# Attenumults_Rev_6.net
KiCad netlist of a schematic drawn in EAGLE
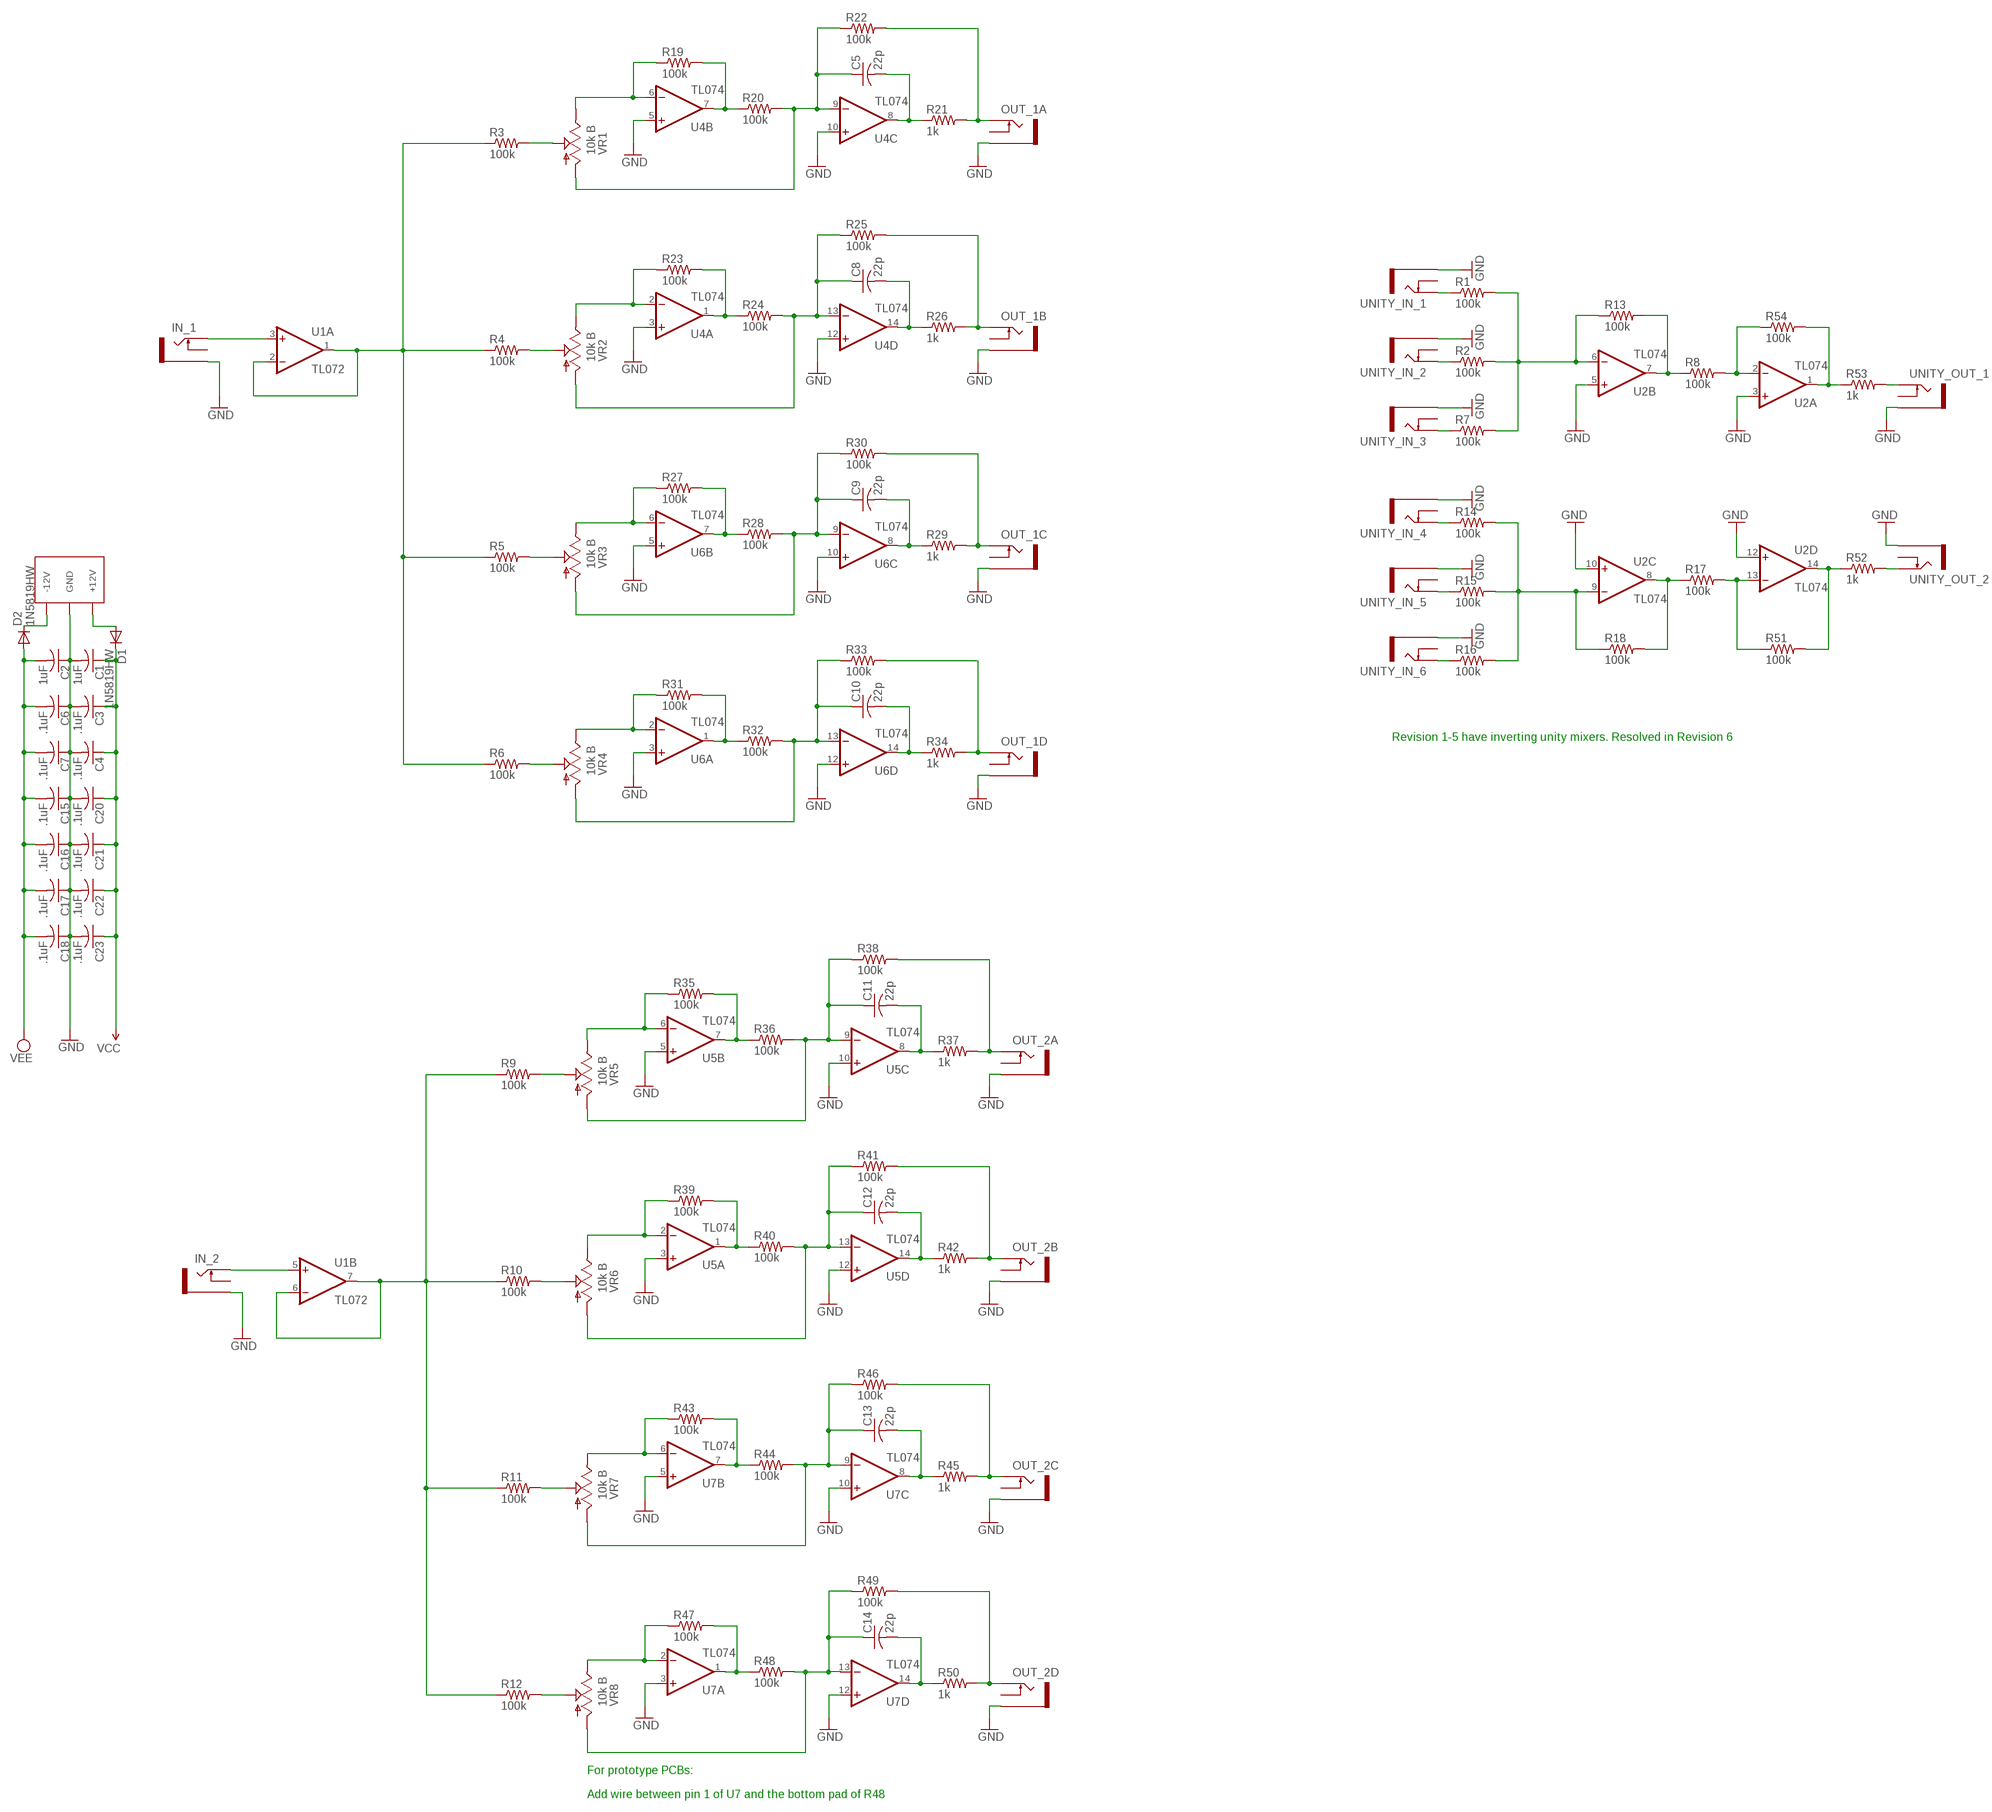
[diagram p0: schematic, sheet 1]

(export (version "E")
  (design (tool "Eeschema 10.0.6"))
  (components
    (comp (ref "C1")
      (value "1uF")
      (footprint "eagle-import:C0805")
      (libsource (lib "eagle-import") (part "C-USC0805"))
    )
    (comp (ref "C2")
      (value "1uF")
      (footprint "eagle-import:C0805")
      (libsource (lib "eagle-import") (part "C-USC0805"))
    )
    (comp (ref "C3")
      (value ".1uF")
      (footprint "eagle-import:C0805")
      (libsource (lib "eagle-import") (part "C-USC0805"))
    )
    (comp (ref "C4")
      (value ".1uF")
      (footprint "eagle-import:C0805")
      (libsource (lib "eagle-import") (part "C-USC0805"))
    )
    (comp (ref "C5")
      (value "22p")
      (footprint "eagle-import:C0805")
      (libsource (lib "eagle-import") (part "C-USC0805"))
    )
    (comp (ref "C6")
      (value ".1uF")
      (footprint "eagle-import:C0805")
      (libsource (lib "eagle-import") (part "C-USC0805"))
    )
    (comp (ref "C7")
      (value ".1uF")
      (footprint "eagle-import:C0805")
      (libsource (lib "eagle-import") (part "C-USC0805"))
    )
    (comp (ref "C8")
      (value "22p")
      (footprint "eagle-import:C0805")
      (libsource (lib "eagle-import") (part "C-USC0805"))
    )
    (comp (ref "C9")
      (value "22p")
      (footprint "eagle-import:C0805")
      (libsource (lib "eagle-import") (part "C-USC0805"))
    )
    (comp (ref "C10")
      (value "22p")
      (footprint "eagle-import:C0805")
      (libsource (lib "eagle-import") (part "C-USC0805"))
    )
    (comp (ref "C11")
      (value "22p")
      (footprint "eagle-import:C0805")
      (libsource (lib "eagle-import") (part "C-USC0805"))
    )
    (comp (ref "C12")
      (value "22p")
      (footprint "eagle-import:C0805")
      (libsource (lib "eagle-import") (part "C-USC0805"))
    )
    (comp (ref "C13")
      (value "22p")
      (footprint "eagle-import:C0805")
      (libsource (lib "eagle-import") (part "C-USC0805"))
    )
    (comp (ref "C14")
      (value "22p")
      (footprint "eagle-import:C0805")
      (libsource (lib "eagle-import") (part "C-USC0805"))
    )
    (comp (ref "C15")
      (value ".1uF")
      (footprint "eagle-import:C0805")
      (libsource (lib "eagle-import") (part "C-USC0805"))
    )
    (comp (ref "C16")
      (value ".1uF")
      (footprint "eagle-import:C0805")
      (libsource (lib "eagle-import") (part "C-USC0805"))
    )
    (comp (ref "C17")
      (value ".1uF")
      (footprint "eagle-import:C0805")
      (libsource (lib "eagle-import") (part "C-USC0805"))
    )
    (comp (ref "C18")
      (value ".1uF")
      (footprint "eagle-import:C0805")
      (libsource (lib "eagle-import") (part "C-USC0805"))
    )
    (comp (ref "C20")
      (value ".1uF")
      (footprint "eagle-import:C0805")
      (libsource (lib "eagle-import") (part "C-USC0805"))
    )
    (comp (ref "C21")
      (value ".1uF")
      (footprint "eagle-import:C0805")
      (libsource (lib "eagle-import") (part "C-USC0805"))
    )
    (comp (ref "C22")
      (value ".1uF")
      (footprint "eagle-import:C0805")
      (libsource (lib "eagle-import") (part "C-USC0805"))
    )
    (comp (ref "C23")
      (value ".1uF")
      (footprint "eagle-import:C0805")
      (libsource (lib "eagle-import") (part "C-USC0805"))
    )
    (comp (ref "D1")
      (value "1N5819HW")
      (footprint "eagle-import:SOD123")
      (libsource (lib "eagle-import") (part "DIODE-SOD123"))
    )
    (comp (ref "D2")
      (value "1N5819HW")
      (footprint "eagle-import:SOD123")
      (libsource (lib "eagle-import") (part "DIODE-SOD123"))
    )
    (comp (ref "IN_1")
      (value "THONKICONNNEW")
      (footprint "eagle-import:WQP-PJ301M-12_JACK")
      (libsource (lib "eagle-import") (part "THONKICONNNEW"))
    )
    (comp (ref "IN_2")
      (value "THONKICONNNEW")
      (footprint "eagle-import:WQP-PJ301M-12_JACK")
      (libsource (lib "eagle-import") (part "THONKICONNNEW"))
    )
    (comp (ref "OUT_1A")
      (value "THONKICONNNEW")
      (footprint "eagle-import:WQP-PJ301M-12_JACK")
      (libsource (lib "eagle-import") (part "THONKICONNNEW"))
    )
    (comp (ref "OUT_1B")
      (value "THONKICONNNEW")
      (footprint "eagle-import:WQP-PJ301M-12_JACK")
      (libsource (lib "eagle-import") (part "THONKICONNNEW"))
    )
    (comp (ref "OUT_1C")
      (value "THONKICONNNEW")
      (footprint "eagle-import:WQP-PJ301M-12_JACK")
      (libsource (lib "eagle-import") (part "THONKICONNNEW"))
    )
    (comp (ref "OUT_1D")
      (value "THONKICONNNEW")
      (footprint "eagle-import:WQP-PJ301M-12_JACK")
      (libsource (lib "eagle-import") (part "THONKICONNNEW"))
    )
    (comp (ref "OUT_2A")
      (value "THONKICONNNEW")
      (footprint "eagle-import:WQP-PJ301M-12_JACK")
      (libsource (lib "eagle-import") (part "THONKICONNNEW"))
    )
    (comp (ref "OUT_2B")
      (value "THONKICONNNEW")
      (footprint "eagle-import:WQP-PJ301M-12_JACK")
      (libsource (lib "eagle-import") (part "THONKICONNNEW"))
    )
    (comp (ref "OUT_2C")
      (value "THONKICONNNEW")
      (footprint "eagle-import:WQP-PJ301M-12_JACK")
      (libsource (lib "eagle-import") (part "THONKICONNNEW"))
    )
    (comp (ref "OUT_2D")
      (value "THONKICONNNEW")
      (footprint "eagle-import:WQP-PJ301M-12_JACK")
      (libsource (lib "eagle-import") (part "THONKICONNNEW"))
    )
    (comp (ref "R1")
      (value "100k")
      (footprint "eagle-import:R0805")
      (libsource (lib "eagle-import") (part "R-US_R0805"))
    )
    (comp (ref "R2")
      (value "100k")
      (footprint "eagle-import:R0805")
      (libsource (lib "eagle-import") (part "R-US_R0805"))
    )
    (comp (ref "R3")
      (value "100k")
      (footprint "eagle-import:R0805")
      (libsource (lib "eagle-import") (part "R-US_R0805"))
    )
    (comp (ref "R4")
      (value "100k")
      (footprint "eagle-import:R0805")
      (libsource (lib "eagle-import") (part "R-US_R0805"))
    )
    (comp (ref "R5")
      (value "100k")
      (footprint "eagle-import:R0805")
      (libsource (lib "eagle-import") (part "R-US_R0805"))
    )
    (comp (ref "R6")
      (value "100k")
      (footprint "eagle-import:R0805")
      (libsource (lib "eagle-import") (part "R-US_R0805"))
    )
    (comp (ref "R7")
      (value "100k")
      (footprint "eagle-import:R0805")
      (libsource (lib "eagle-import") (part "R-US_R0805"))
    )
    (comp (ref "R8")
      (value "100k")
      (footprint "eagle-import:R0805")
      (libsource (lib "eagle-import") (part "R-US_R0805"))
    )
    (comp (ref "R9")
      (value "100k")
      (footprint "eagle-import:R0805")
      (libsource (lib "eagle-import") (part "R-US_R0805"))
    )
    (comp (ref "R10")
      (value "100k")
      (footprint "eagle-import:R0805")
      (libsource (lib "eagle-import") (part "R-US_R0805"))
    )
    (comp (ref "R11")
      (value "100k")
      (footprint "eagle-import:R0805")
      (libsource (lib "eagle-import") (part "R-US_R0805"))
    )
    (comp (ref "R12")
      (value "100k")
      (footprint "eagle-import:R0805")
      (libsource (lib "eagle-import") (part "R-US_R0805"))
    )
    (comp (ref "R13")
      (value "100k")
      (footprint "eagle-import:R0805")
      (libsource (lib "eagle-import") (part "R-US_R0805"))
    )
    (comp (ref "R14")
      (value "100k")
      (footprint "eagle-import:R0805")
      (libsource (lib "eagle-import") (part "R-US_R0805"))
    )
    (comp (ref "R15")
      (value "100k")
      (footprint "eagle-import:R0805")
      (libsource (lib "eagle-import") (part "R-US_R0805"))
    )
    (comp (ref "R16")
      (value "100k")
      (footprint "eagle-import:R0805")
      (libsource (lib "eagle-import") (part "R-US_R0805"))
    )
    (comp (ref "R17")
      (value "100k")
      (footprint "eagle-import:R0805")
      (libsource (lib "eagle-import") (part "R-US_R0805"))
    )
    (comp (ref "R18")
      (value "100k")
      (footprint "eagle-import:R0805")
      (libsource (lib "eagle-import") (part "R-US_R0805"))
    )
    (comp (ref "R19")
      (value "100k")
      (footprint "eagle-import:R0805")
      (libsource (lib "eagle-import") (part "R-US_R0805"))
    )
    (comp (ref "R20")
      (value "100k")
      (footprint "eagle-import:R0805")
      (libsource (lib "eagle-import") (part "R-US_R0805"))
    )
    (comp (ref "R21")
      (value "1k")
      (footprint "eagle-import:R0805")
      (libsource (lib "eagle-import") (part "R-US_R0805"))
    )
    (comp (ref "R22")
      (value "100k")
      (footprint "eagle-import:R0805")
      (libsource (lib "eagle-import") (part "R-US_R0805"))
    )
    (comp (ref "R23")
      (value "100k")
      (footprint "eagle-import:R0805")
      (libsource (lib "eagle-import") (part "R-US_R0805"))
    )
    (comp (ref "R24")
      (value "100k")
      (footprint "eagle-import:R0805")
      (libsource (lib "eagle-import") (part "R-US_R0805"))
    )
    (comp (ref "R25")
      (value "100k")
      (footprint "eagle-import:R0805")
      (libsource (lib "eagle-import") (part "R-US_R0805"))
    )
    (comp (ref "R26")
      (value "1k")
      (footprint "eagle-import:R0805")
      (libsource (lib "eagle-import") (part "R-US_R0805"))
    )
    (comp (ref "R27")
      (value "100k")
      (footprint "eagle-import:R0805")
      (libsource (lib "eagle-import") (part "R-US_R0805"))
    )
    (comp (ref "R28")
      (value "100k")
      (footprint "eagle-import:R0805")
      (libsource (lib "eagle-import") (part "R-US_R0805"))
    )
    (comp (ref "R29")
      (value "1k")
      (footprint "eagle-import:R0805")
      (libsource (lib "eagle-import") (part "R-US_R0805"))
    )
    (comp (ref "R30")
      (value "100k")
      (footprint "eagle-import:R0805")
      (libsource (lib "eagle-import") (part "R-US_R0805"))
    )
    (comp (ref "R31")
      (value "100k")
      (footprint "eagle-import:R0805")
      (libsource (lib "eagle-import") (part "R-US_R0805"))
    )
    (comp (ref "R32")
      (value "100k")
      (footprint "eagle-import:R0805")
      (libsource (lib "eagle-import") (part "R-US_R0805"))
    )
    (comp (ref "R33")
      (value "100k")
      (footprint "eagle-import:R0805")
      (libsource (lib "eagle-import") (part "R-US_R0805"))
    )
    (comp (ref "R34")
      (value "1k")
      (footprint "eagle-import:R0805")
      (libsource (lib "eagle-import") (part "R-US_R0805"))
    )
    (comp (ref "R35")
      (value "100k")
      (footprint "eagle-import:R0805")
      (libsource (lib "eagle-import") (part "R-US_R0805"))
    )
    (comp (ref "R36")
      (value "100k")
      (footprint "eagle-import:R0805")
      (libsource (lib "eagle-import") (part "R-US_R0805"))
    )
    (comp (ref "R37")
      (value "1k")
      (footprint "eagle-import:R0805")
      (libsource (lib "eagle-import") (part "R-US_R0805"))
    )
    (comp (ref "R38")
      (value "100k")
      (footprint "eagle-import:R0805")
      (libsource (lib "eagle-import") (part "R-US_R0805"))
    )
    (comp (ref "R39")
      (value "100k")
      (footprint "eagle-import:R0805")
      (libsource (lib "eagle-import") (part "R-US_R0805"))
    )
    (comp (ref "R40")
      (value "100k")
      (footprint "eagle-import:R0805")
      (libsource (lib "eagle-import") (part "R-US_R0805"))
    )
    (comp (ref "R41")
      (value "100k")
      (footprint "eagle-import:R0805")
      (libsource (lib "eagle-import") (part "R-US_R0805"))
    )
    (comp (ref "R42")
      (value "1k")
      (footprint "eagle-import:R0805")
      (libsource (lib "eagle-import") (part "R-US_R0805"))
    )
    (comp (ref "R43")
      (value "100k")
      (footprint "eagle-import:R0805")
      (libsource (lib "eagle-import") (part "R-US_R0805"))
    )
    (comp (ref "R44")
      (value "100k")
      (footprint "eagle-import:R0805")
      (libsource (lib "eagle-import") (part "R-US_R0805"))
    )
    (comp (ref "R45")
      (value "1k")
      (footprint "eagle-import:R0805")
      (libsource (lib "eagle-import") (part "R-US_R0805"))
    )
    (comp (ref "R46")
      (value "100k")
      (footprint "eagle-import:R0805")
      (libsource (lib "eagle-import") (part "R-US_R0805"))
    )
    (comp (ref "R47")
      (value "100k")
      (footprint "eagle-import:R0805")
      (libsource (lib "eagle-import") (part "R-US_R0805"))
    )
    (comp (ref "R48")
      (value "100k")
      (footprint "eagle-import:R0805")
      (libsource (lib "eagle-import") (part "R-US_R0805"))
    )
    (comp (ref "R49")
      (value "100k")
      (footprint "eagle-import:R0805")
      (libsource (lib "eagle-import") (part "R-US_R0805"))
    )
    (comp (ref "R50")
      (value "1k")
      (footprint "eagle-import:R0805")
      (libsource (lib "eagle-import") (part "R-US_R0805"))
    )
    (comp (ref "R51")
      (value "100k")
      (footprint "eagle-import:R0805")
      (libsource (lib "eagle-import") (part "R-US_R0805"))
    )
    (comp (ref "R52")
      (value "1k")
      (footprint "eagle-import:R0805")
      (libsource (lib "eagle-import") (part "R-US_R0805"))
    )
    (comp (ref "R53")
      (value "1k")
      (footprint "eagle-import:R0805")
      (libsource (lib "eagle-import") (part "R-US_R0805"))
    )
    (comp (ref "R54")
      (value "100k")
      (footprint "eagle-import:R0805")
      (libsource (lib "eagle-import") (part "R-US_R0805"))
    )
    (comp (ref "U$1")
      (value "EURO_POWER_LOCK")
      (footprint "eagle-import:EURO_PWR_HEADER_LOCK")
      (libsource (lib "eagle-import") (part "EURO_POWER_LOCK"))
    )
    (comp (ref "U1")
      (value "TL072")
      (footprint "eagle-import:SO08")
      (libsource (lib "eagle-import") (part "TL072_SMD"))
    )
    (comp (ref "U2")
      (value "TL074")
      (footprint "eagle-import:SO14")
      (libsource (lib "eagle-import") (part "TL074_SMD"))
    )
    (comp (ref "U4")
      (value "TL074")
      (footprint "eagle-import:SO14")
      (libsource (lib "eagle-import") (part "TL074_SMD"))
    )
    (comp (ref "U5")
      (value "TL074")
      (footprint "eagle-import:SO14")
      (libsource (lib "eagle-import") (part "TL074_SMD"))
    )
    (comp (ref "U6")
      (value "TL074")
      (footprint "eagle-import:SO14")
      (libsource (lib "eagle-import") (part "TL074_SMD"))
    )
    (comp (ref "U7")
      (value "TL074")
      (footprint "eagle-import:SO14")
      (libsource (lib "eagle-import") (part "TL074_SMD"))
    )
    (comp (ref "UNITY_IN_1")
      (value "THONKICONNNEW")
      (footprint "eagle-import:WQP-PJ301M-12_JACK")
      (libsource (lib "eagle-import") (part "THONKICONNNEW"))
    )
    (comp (ref "UNITY_IN_2")
      (value "THONKICONNNEW")
      (footprint "eagle-import:WQP-PJ301M-12_JACK")
      (libsource (lib "eagle-import") (part "THONKICONNNEW"))
    )
    (comp (ref "UNITY_IN_3")
      (value "THONKICONNNEW")
      (footprint "eagle-import:WQP-PJ301M-12_JACK")
      (libsource (lib "eagle-import") (part "THONKICONNNEW"))
    )
    (comp (ref "UNITY_IN_4")
      (value "THONKICONNNEW")
      (footprint "eagle-import:WQP-PJ301M-12_JACK")
      (libsource (lib "eagle-import") (part "THONKICONNNEW"))
    )
    (comp (ref "UNITY_IN_5")
      (value "THONKICONNNEW")
      (footprint "eagle-import:WQP-PJ301M-12_JACK")
      (libsource (lib "eagle-import") (part "THONKICONNNEW"))
    )
    (comp (ref "UNITY_IN_6")
      (value "THONKICONNNEW")
      (footprint "eagle-import:WQP-PJ301M-12_JACK")
      (libsource (lib "eagle-import") (part "THONKICONNNEW"))
    )
    (comp (ref "UNITY_OUT_1")
      (value "THONKICONNNEW")
      (footprint "eagle-import:WQP-PJ301M-12_JACK")
      (libsource (lib "eagle-import") (part "THONKICONNNEW"))
    )
    (comp (ref "UNITY_OUT_2")
      (value "THONKICONNNEW")
      (footprint "eagle-import:WQP-PJ301M-12_JACK")
      (libsource (lib "eagle-import") (part "THONKICONNNEW"))
    )
    (comp (ref "VR1")
      (value "10k B")
      (footprint "eagle-import:ALPS_POT_VERTICAL_PS")
      (libsource (lib "eagle-import") (part "POT_USVERTICAL_PS"))
    )
    (comp (ref "VR2")
      (value "10k B")
      (footprint "eagle-import:ALPS_POT_VERTICAL_PS")
      (libsource (lib "eagle-import") (part "POT_USVERTICAL_PS"))
    )
    (comp (ref "VR3")
      (value "10k B")
      (footprint "eagle-import:ALPS_POT_VERTICAL_PS")
      (libsource (lib "eagle-import") (part "POT_USVERTICAL_PS"))
    )
    (comp (ref "VR4")
      (value "10k B")
      (footprint "eagle-import:ALPS_POT_VERTICAL_PS")
      (libsource (lib "eagle-import") (part "POT_USVERTICAL_PS"))
    )
    (comp (ref "VR5")
      (value "10k B")
      (footprint "eagle-import:ALPS_POT_VERTICAL_PS")
      (libsource (lib "eagle-import") (part "POT_USVERTICAL_PS"))
    )
    (comp (ref "VR6")
      (value "10k B")
      (footprint "eagle-import:ALPS_POT_VERTICAL_PS")
      (libsource (lib "eagle-import") (part "POT_USVERTICAL_PS"))
    )
    (comp (ref "VR7")
      (value "10k B")
      (footprint "eagle-import:ALPS_POT_VERTICAL_PS")
      (libsource (lib "eagle-import") (part "POT_USVERTICAL_PS"))
    )
    (comp (ref "VR8")
      (value "10k B")
      (footprint "eagle-import:ALPS_POT_VERTICAL_PS")
      (libsource (lib "eagle-import") (part "POT_USVERTICAL_PS"))
    )
  )
  (nets
    (net (code "1") (name "GND") (class "Default")
      (node (ref "C1") (pin "2") (pinfunction "2_2") (pintype "passive"))
      (node (ref "C15") (pin "1") (pinfunction "1_1") (pintype "passive"))
      (node (ref "C16") (pin "1") (pinfunction "1_1") (pintype "passive"))
      (node (ref "C17") (pin "1") (pinfunction "1_1") (pintype "passive"))
      (node (ref "C18") (pin "1") (pinfunction "1_1") (pintype "passive"))
      (node (ref "C2") (pin "1") (pinfunction "1_1") (pintype "passive"))
      (node (ref "C20") (pin "2") (pinfunction "2_2") (pintype "passive"))
      (node (ref "C21") (pin "2") (pinfunction "2_2") (pintype "passive"))
      (node (ref "C22") (pin "2") (pinfunction "2_2") (pintype "passive"))
      (node (ref "C23") (pin "2") (pinfunction "2_2") (pintype "passive"))
      (node (ref "C3") (pin "2") (pinfunction "2_2") (pintype "passive"))
      (node (ref "C4") (pin "2") (pinfunction "2_2") (pintype "passive"))
      (node (ref "C6") (pin "1") (pinfunction "1_1") (pintype "passive"))
      (node (ref "C7") (pin "1") (pinfunction "1_1") (pintype "passive"))
      (node (ref "IN_1") (pin "P$3_SLEEVE") (pinfunction "SLEEVE_P$3_SLEEVE") (pintype "passive"))
      (node (ref "IN_2") (pin "P$3_SLEEVE") (pinfunction "SLEEVE_P$3_SLEEVE") (pintype "passive"))
      (node (ref "OUT_1A") (pin "P$3_SLEEVE") (pinfunction "SLEEVE_P$3_SLEEVE") (pintype "passive"))
      (node (ref "OUT_1B") (pin "P$3_SLEEVE") (pinfunction "SLEEVE_P$3_SLEEVE") (pintype "passive"))
      (node (ref "OUT_1C") (pin "P$3_SLEEVE") (pinfunction "SLEEVE_P$3_SLEEVE") (pintype "passive"))
      (node (ref "OUT_1D") (pin "P$3_SLEEVE") (pinfunction "SLEEVE_P$3_SLEEVE") (pintype "passive"))
      (node (ref "OUT_2A") (pin "P$3_SLEEVE") (pinfunction "SLEEVE_P$3_SLEEVE") (pintype "passive"))
      (node (ref "OUT_2B") (pin "P$3_SLEEVE") (pinfunction "SLEEVE_P$3_SLEEVE") (pintype "passive"))
      (node (ref "OUT_2C") (pin "P$3_SLEEVE") (pinfunction "SLEEVE_P$3_SLEEVE") (pintype "passive"))
      (node (ref "OUT_2D") (pin "P$3_SLEEVE") (pinfunction "SLEEVE_P$3_SLEEVE") (pintype "passive"))
      (node (ref "U$1") (pin "GND1") (pinfunction "GND_GND1") (pintype "bidirectional"))
      (node (ref "U$1") (pin "GND2") (pinfunction "GND_GND2") (pintype "bidirectional"))
      (node (ref "U$1") (pin "GND3") (pinfunction "GND_GND3") (pintype "bidirectional"))
      (node (ref "U$1") (pin "GND4") (pinfunction "GND_GND4") (pintype "bidirectional"))
      (node (ref "U$1") (pin "GND5") (pinfunction "GND_GND5") (pintype "bidirectional"))
      (node (ref "U$1") (pin "GND6") (pinfunction "GND_GND6") (pintype "bidirectional"))
      (node (ref "U2") (pin "10") (pinfunction "+IN_10") (pintype "input"))
      (node (ref "U2") (pin "12") (pinfunction "+IN_12") (pintype "input"))
      (node (ref "U2") (pin "3") (pinfunction "+IN_3") (pintype "input"))
      (node (ref "U2") (pin "5") (pinfunction "+IN_5") (pintype "input"))
      (node (ref "U4") (pin "10") (pinfunction "+IN_10") (pintype "input"))
      (node (ref "U4") (pin "12") (pinfunction "+IN_12") (pintype "input"))
      (node (ref "U4") (pin "3") (pinfunction "+IN_3") (pintype "input"))
      (node (ref "U4") (pin "5") (pinfunction "+IN_5") (pintype "input"))
      (node (ref "U5") (pin "10") (pinfunction "+IN_10") (pintype "input"))
      (node (ref "U5") (pin "12") (pinfunction "+IN_12") (pintype "input"))
      (node (ref "U5") (pin "3") (pinfunction "+IN_3") (pintype "input"))
      (node (ref "U5") (pin "5") (pinfunction "+IN_5") (pintype "input"))
      (node (ref "U6") (pin "10") (pinfunction "+IN_10") (pintype "input"))
      (node (ref "U6") (pin "12") (pinfunction "+IN_12") (pintype "input"))
      (node (ref "U6") (pin "3") (pinfunction "+IN_3") (pintype "input"))
      (node (ref "U6") (pin "5") (pinfunction "+IN_5") (pintype "input"))
      (node (ref "U7") (pin "10") (pinfunction "+IN_10") (pintype "input"))
      (node (ref "U7") (pin "12") (pinfunction "+IN_12") (pintype "input"))
      (node (ref "U7") (pin "3") (pinfunction "+IN_3") (pintype "input"))
      (node (ref "U7") (pin "5") (pinfunction "+IN_5") (pintype "input"))
      (node (ref "UNITY_IN_1") (pin "P$3_SLEEVE") (pinfunction "SLEEVE_P$3_SLEEVE") (pintype "passive"))
      (node (ref "UNITY_IN_2") (pin "P$3_SLEEVE") (pinfunction "SLEEVE_P$3_SLEEVE") (pintype "passive"))
      (node (ref "UNITY_IN_3") (pin "P$3_SLEEVE") (pinfunction "SLEEVE_P$3_SLEEVE") (pintype "passive"))
      (node (ref "UNITY_IN_4") (pin "P$3_SLEEVE") (pinfunction "SLEEVE_P$3_SLEEVE") (pintype "passive"))
      (node (ref "UNITY_IN_5") (pin "P$3_SLEEVE") (pinfunction "SLEEVE_P$3_SLEEVE") (pintype "passive"))
      (node (ref "UNITY_IN_6") (pin "P$3_SLEEVE") (pinfunction "SLEEVE_P$3_SLEEVE") (pintype "passive"))
      (node (ref "UNITY_OUT_1") (pin "P$3_SLEEVE") (pinfunction "SLEEVE_P$3_SLEEVE") (pintype "passive"))
      (node (ref "UNITY_OUT_2") (pin "P$3_SLEEVE") (pinfunction "SLEEVE_P$3_SLEEVE") (pintype "passive"))
    )
    (net (code "2") (name "Net-(D1-PadA)") (class "Default")
      (node (ref "D1") (pin "A") (pinfunction "A_A") (pintype "passive"))
      (node (ref "U$1") (pin "POS1") (pinfunction "+12V_POS1") (pintype "bidirectional"))
      (node (ref "U$1") (pin "POS2") (pinfunction "+12V_POS2") (pintype "bidirectional"))
    )
    (net (code "3") (name "Net-(D2-PadC)") (class "Default")
      (node (ref "D2") (pin "C") (pinfunction "C_C") (pintype "passive"))
      (node (ref "U$1") (pin "NEG1") (pinfunction "-12V_NEG1") (pintype "bidirectional"))
      (node (ref "U$1") (pin "NEG2") (pinfunction "-12V_NEG2") (pintype "bidirectional"))
    )
    (net (code "4") (name "Net-(IN_1-TIP)") (class "Default")
      (node (ref "IN_1") (pin "P$1_TIP") (pinfunction "TIP_P$1_TIP") (pintype "passive"))
      (node (ref "U1") (pin "3") (pinfunction "+IN_3") (pintype "input"))
    )
    (net (code "5") (name "Net-(IN_2-TIP)") (class "Default")
      (node (ref "IN_2") (pin "P$1_TIP") (pinfunction "TIP_P$1_TIP") (pintype "passive"))
      (node (ref "U1") (pin "5") (pinfunction "+IN_5") (pintype "input"))
    )
    (net (code "6") (name "Net-(OUT_1A-TIP)") (class "Default")
      (node (ref "OUT_1A") (pin "P$1_TIP") (pinfunction "TIP_P$1_TIP") (pintype "passive"))
      (node (ref "R21") (pin "2") (pinfunction "2_2") (pintype "passive"))
      (node (ref "R22") (pin "2") (pinfunction "2_2") (pintype "passive"))
    )
    (net (code "7") (name "Net-(OUT_1B-TIP)") (class "Default")
      (node (ref "OUT_1B") (pin "P$1_TIP") (pinfunction "TIP_P$1_TIP") (pintype "passive"))
      (node (ref "R25") (pin "2") (pinfunction "2_2") (pintype "passive"))
      (node (ref "R26") (pin "2") (pinfunction "2_2") (pintype "passive"))
    )
    (net (code "8") (name "Net-(OUT_1C-TIP)") (class "Default")
      (node (ref "OUT_1C") (pin "P$1_TIP") (pinfunction "TIP_P$1_TIP") (pintype "passive"))
      (node (ref "R29") (pin "2") (pinfunction "2_2") (pintype "passive"))
      (node (ref "R30") (pin "2") (pinfunction "2_2") (pintype "passive"))
    )
    (net (code "9") (name "Net-(OUT_1D-TIP)") (class "Default")
      (node (ref "OUT_1D") (pin "P$1_TIP") (pinfunction "TIP_P$1_TIP") (pintype "passive"))
      (node (ref "R33") (pin "2") (pinfunction "2_2") (pintype "passive"))
      (node (ref "R34") (pin "2") (pinfunction "2_2") (pintype "passive"))
    )
    (net (code "10") (name "Net-(OUT_2A-TIP)") (class "Default")
      (node (ref "OUT_2A") (pin "P$1_TIP") (pinfunction "TIP_P$1_TIP") (pintype "passive"))
      (node (ref "R37") (pin "2") (pinfunction "2_2") (pintype "passive"))
      (node (ref "R38") (pin "2") (pinfunction "2_2") (pintype "passive"))
    )
    (net (code "11") (name "Net-(OUT_2B-TIP)") (class "Default")
      (node (ref "OUT_2B") (pin "P$1_TIP") (pinfunction "TIP_P$1_TIP") (pintype "passive"))
      (node (ref "R41") (pin "2") (pinfunction "2_2") (pintype "passive"))
      (node (ref "R42") (pin "2") (pinfunction "2_2") (pintype "passive"))
    )
    (net (code "12") (name "Net-(OUT_2C-TIP)") (class "Default")
      (node (ref "OUT_2C") (pin "P$1_TIP") (pinfunction "TIP_P$1_TIP") (pintype "passive"))
      (node (ref "R45") (pin "2") (pinfunction "2_2") (pintype "passive"))
      (node (ref "R46") (pin "2") (pinfunction "2_2") (pintype "passive"))
    )
    (net (code "13") (name "Net-(OUT_2D-TIP)") (class "Default")
      (node (ref "OUT_2D") (pin "P$1_TIP") (pinfunction "TIP_P$1_TIP") (pintype "passive"))
      (node (ref "R49") (pin "2") (pinfunction "2_2") (pintype "passive"))
      (node (ref "R50") (pin "2") (pinfunction "2_2") (pintype "passive"))
    )
    (net (code "14") (name "Net-(U1A--IN)") (class "Default")
      (node (ref "R3") (pin "1") (pinfunction "1_1") (pintype "passive"))
      (node (ref "R4") (pin "1") (pinfunction "1_1") (pintype "passive"))
      (node (ref "R5") (pin "1") (pinfunction "1_1") (pintype "passive"))
      (node (ref "R6") (pin "1") (pinfunction "1_1") (pintype "passive"))
      (node (ref "U1") (pin "1") (pinfunction "OUT_1") (pintype "output"))
      (node (ref "U1") (pin "2") (pinfunction "-IN_2") (pintype "input"))
    )
    (net (code "15") (name "Net-(U1B--IN)") (class "Default")
      (node (ref "R10") (pin "1") (pinfunction "1_1") (pintype "passive"))
      (node (ref "R11") (pin "1") (pinfunction "1_1") (pintype "passive"))
      (node (ref "R12") (pin "1") (pinfunction "1_1") (pintype "passive"))
      (node (ref "R9") (pin "1") (pinfunction "1_1") (pintype "passive"))
      (node (ref "U1") (pin "6") (pinfunction "-IN_6") (pintype "input"))
      (node (ref "U1") (pin "7") (pinfunction "OUT_7") (pintype "output"))
    )
    (net (code "16") (name "Net-(U2A--IN)") (class "Default")
      (node (ref "R54") (pin "1") (pinfunction "1_1") (pintype "passive"))
      (node (ref "R8") (pin "2") (pinfunction "2_2") (pintype "passive"))
      (node (ref "U2") (pin "2") (pinfunction "-IN_2") (pintype "input"))
    )
    (net (code "17") (name "Net-(U2A-OUT)") (class "Default")
      (node (ref "R53") (pin "1") (pinfunction "1_1") (pintype "passive"))
      (node (ref "R54") (pin "2") (pinfunction "2_2") (pintype "passive"))
      (node (ref "U2") (pin "1") (pinfunction "OUT_1") (pintype "output"))
    )
    (net (code "18") (name "Net-(U2B--IN)") (class "Default")
      (node (ref "R1") (pin "2") (pinfunction "2_2") (pintype "passive"))
      (node (ref "R13") (pin "1") (pinfunction "1_1") (pintype "passive"))
      (node (ref "R2") (pin "2") (pinfunction "2_2") (pintype "passive"))
      (node (ref "R7") (pin "2") (pinfunction "2_2") (pintype "passive"))
      (node (ref "U2") (pin "6") (pinfunction "-IN_6") (pintype "input"))
    )
    (net (code "19") (name "Net-(U2B-OUT)") (class "Default")
      (node (ref "R13") (pin "2") (pinfunction "2_2") (pintype "passive"))
      (node (ref "R8") (pin "1") (pinfunction "1_1") (pintype "passive"))
      (node (ref "U2") (pin "7") (pinfunction "OUT_7") (pintype "output"))
    )
    (net (code "20") (name "Net-(U2C--IN)") (class "Default")
      (node (ref "R14") (pin "2") (pinfunction "2_2") (pintype "passive"))
      (node (ref "R15") (pin "2") (pinfunction "2_2") (pintype "passive"))
      (node (ref "R16") (pin "2") (pinfunction "2_2") (pintype "passive"))
      (node (ref "R18") (pin "1") (pinfunction "1_1") (pintype "passive"))
      (node (ref "U2") (pin "9") (pinfunction "-IN_9") (pintype "input"))
    )
    (net (code "21") (name "Net-(U2C-OUT)") (class "Default")
      (node (ref "R17") (pin "1") (pinfunction "1_1") (pintype "passive"))
      (node (ref "R18") (pin "2") (pinfunction "2_2") (pintype "passive"))
      (node (ref "U2") (pin "8") (pinfunction "OUT_8") (pintype "output"))
    )
    (net (code "22") (name "Net-(U2D--IN)") (class "Default")
      (node (ref "R17") (pin "2") (pinfunction "2_2") (pintype "passive"))
      (node (ref "R51") (pin "1") (pinfunction "1_1") (pintype "passive"))
      (node (ref "U2") (pin "13") (pinfunction "-IN_13") (pintype "input"))
    )
    (net (code "23") (name "Net-(U2D-OUT)") (class "Default")
      (node (ref "R51") (pin "2") (pinfunction "2_2") (pintype "passive"))
      (node (ref "R52") (pin "1") (pinfunction "1_1") (pintype "passive"))
      (node (ref "U2") (pin "14") (pinfunction "OUT_14") (pintype "output"))
    )
    (net (code "24") (name "Net-(U4A--IN)") (class "Default")
      (node (ref "R23") (pin "1") (pinfunction "1_1") (pintype "passive"))
      (node (ref "U4") (pin "2") (pinfunction "-IN_2") (pintype "input"))
      (node (ref "VR2") (pin "P$1") (pinfunction "E_P$1") (pintype "passive"))
    )
    (net (code "25") (name "Net-(U4A-OUT)") (class "Default")
      (node (ref "R23") (pin "2") (pinfunction "2_2") (pintype "passive"))
      (node (ref "R24") (pin "1") (pinfunction "1_1") (pintype "passive"))
      (node (ref "U4") (pin "1") (pinfunction "OUT_1") (pintype "output"))
    )
    (net (code "26") (name "Net-(U4B--IN)") (class "Default")
      (node (ref "R19") (pin "1") (pinfunction "1_1") (pintype "passive"))
      (node (ref "U4") (pin "6") (pinfunction "-IN_6") (pintype "input"))
      (node (ref "VR1") (pin "P$1") (pinfunction "E_P$1") (pintype "passive"))
    )
    (net (code "27") (name "Net-(U4B-OUT)") (class "Default")
      (node (ref "R19") (pin "2") (pinfunction "2_2") (pintype "passive"))
      (node (ref "R20") (pin "1") (pinfunction "1_1") (pintype "passive"))
      (node (ref "U4") (pin "7") (pinfunction "OUT_7") (pintype "output"))
    )
    (net (code "28") (name "Net-(U4C--IN)") (class "Default")
      (node (ref "C5") (pin "1") (pinfunction "1_1") (pintype "passive"))
      (node (ref "R20") (pin "2") (pinfunction "2_2") (pintype "passive"))
      (node (ref "R22") (pin "1") (pinfunction "1_1") (pintype "passive"))
      (node (ref "U4") (pin "9") (pinfunction "-IN_9") (pintype "input"))
      (node (ref "VR1") (pin "P$3") (pinfunction "A_P$3") (pintype "passive"))
    )
    (net (code "29") (name "Net-(U4C-OUT)") (class "Default")
      (node (ref "C5") (pin "2") (pinfunction "2_2") (pintype "passive"))
      (node (ref "R21") (pin "1") (pinfunction "1_1") (pintype "passive"))
      (node (ref "U4") (pin "8") (pinfunction "OUT_8") (pintype "output"))
    )
    (net (code "30") (name "Net-(U4D--IN)") (class "Default")
      (node (ref "C8") (pin "1") (pinfunction "1_1") (pintype "passive"))
      (node (ref "R24") (pin "2") (pinfunction "2_2") (pintype "passive"))
      (node (ref "R25") (pin "1") (pinfunction "1_1") (pintype "passive"))
      (node (ref "U4") (pin "13") (pinfunction "-IN_13") (pintype "input"))
      (node (ref "VR2") (pin "P$3") (pinfunction "A_P$3") (pintype "passive"))
    )
    (net (code "31") (name "Net-(U4D-OUT)") (class "Default")
      (node (ref "C8") (pin "2") (pinfunction "2_2") (pintype "passive"))
      (node (ref "R26") (pin "1") (pinfunction "1_1") (pintype "passive"))
      (node (ref "U4") (pin "14") (pinfunction "OUT_14") (pintype "output"))
    )
    (net (code "32") (name "Net-(U5A--IN)") (class "Default")
      (node (ref "R39") (pin "1") (pinfunction "1_1") (pintype "passive"))
      (node (ref "U5") (pin "2") (pinfunction "-IN_2") (pintype "input"))
      (node (ref "VR6") (pin "P$1") (pinfunction "E_P$1") (pintype "passive"))
    )
    (net (code "33") (name "Net-(U5A-OUT)") (class "Default")
      (node (ref "R39") (pin "2") (pinfunction "2_2") (pintype "passive"))
      (node (ref "R40") (pin "1") (pinfunction "1_1") (pintype "passive"))
      (node (ref "U5") (pin "1") (pinfunction "OUT_1") (pintype "output"))
    )
    (net (code "34") (name "Net-(U5B--IN)") (class "Default")
      (node (ref "R35") (pin "1") (pinfunction "1_1") (pintype "passive"))
      (node (ref "U5") (pin "6") (pinfunction "-IN_6") (pintype "input"))
      (node (ref "VR5") (pin "P$1") (pinfunction "E_P$1") (pintype "passive"))
    )
    (net (code "35") (name "Net-(U5B-OUT)") (class "Default")
      (node (ref "R35") (pin "2") (pinfunction "2_2") (pintype "passive"))
      (node (ref "R36") (pin "1") (pinfunction "1_1") (pintype "passive"))
      (node (ref "U5") (pin "7") (pinfunction "OUT_7") (pintype "output"))
    )
    (net (code "36") (name "Net-(U5C--IN)") (class "Default")
      (node (ref "C11") (pin "1") (pinfunction "1_1") (pintype "passive"))
      (node (ref "R36") (pin "2") (pinfunction "2_2") (pintype "passive"))
      (node (ref "R38") (pin "1") (pinfunction "1_1") (pintype "passive"))
      (node (ref "U5") (pin "9") (pinfunction "-IN_9") (pintype "input"))
      (node (ref "VR5") (pin "P$3") (pinfunction "A_P$3") (pintype "passive"))
    )
    (net (code "37") (name "Net-(U5C-OUT)") (class "Default")
      (node (ref "C11") (pin "2") (pinfunction "2_2") (pintype "passive"))
      (node (ref "R37") (pin "1") (pinfunction "1_1") (pintype "passive"))
      (node (ref "U5") (pin "8") (pinfunction "OUT_8") (pintype "output"))
    )
    (net (code "38") (name "Net-(U5D--IN)") (class "Default")
      (node (ref "C12") (pin "1") (pinfunction "1_1") (pintype "passive"))
      (node (ref "R40") (pin "2") (pinfunction "2_2") (pintype "passive"))
      (node (ref "R41") (pin "1") (pinfunction "1_1") (pintype "passive"))
      (node (ref "U5") (pin "13") (pinfunction "-IN_13") (pintype "input"))
      (node (ref "VR6") (pin "P$3") (pinfunction "A_P$3") (pintype "passive"))
    )
    (net (code "39") (name "Net-(U5D-OUT)") (class "Default")
      (node (ref "C12") (pin "2") (pinfunction "2_2") (pintype "passive"))
      (node (ref "R42") (pin "1") (pinfunction "1_1") (pintype "passive"))
      (node (ref "U5") (pin "14") (pinfunction "OUT_14") (pintype "output"))
    )
    (net (code "40") (name "Net-(U6A--IN)") (class "Default")
      (node (ref "R31") (pin "1") (pinfunction "1_1") (pintype "passive"))
      (node (ref "U6") (pin "2") (pinfunction "-IN_2") (pintype "input"))
      (node (ref "VR4") (pin "P$1") (pinfunction "E_P$1") (pintype "passive"))
    )
    (net (code "41") (name "Net-(U6A-OUT)") (class "Default")
      (node (ref "R31") (pin "2") (pinfunction "2_2") (pintype "passive"))
      (node (ref "R32") (pin "1") (pinfunction "1_1") (pintype "passive"))
      (node (ref "U6") (pin "1") (pinfunction "OUT_1") (pintype "output"))
    )
    (net (code "42") (name "Net-(U6B--IN)") (class "Default")
      (node (ref "R27") (pin "1") (pinfunction "1_1") (pintype "passive"))
      (node (ref "U6") (pin "6") (pinfunction "-IN_6") (pintype "input"))
      (node (ref "VR3") (pin "P$1") (pinfunction "E_P$1") (pintype "passive"))
    )
    (net (code "43") (name "Net-(U6B-OUT)") (class "Default")
      (node (ref "R27") (pin "2") (pinfunction "2_2") (pintype "passive"))
      (node (ref "R28") (pin "1") (pinfunction "1_1") (pintype "passive"))
      (node (ref "U6") (pin "7") (pinfunction "OUT_7") (pintype "output"))
    )
    (net (code "44") (name "Net-(U6C--IN)") (class "Default")
      (node (ref "C9") (pin "1") (pinfunction "1_1") (pintype "passive"))
      (node (ref "R28") (pin "2") (pinfunction "2_2") (pintype "passive"))
      (node (ref "R30") (pin "1") (pinfunction "1_1") (pintype "passive"))
      (node (ref "U6") (pin "9") (pinfunction "-IN_9") (pintype "input"))
      (node (ref "VR3") (pin "P$3") (pinfunction "A_P$3") (pintype "passive"))
    )
    (net (code "45") (name "Net-(U6C-OUT)") (class "Default")
      (node (ref "C9") (pin "2") (pinfunction "2_2") (pintype "passive"))
      (node (ref "R29") (pin "1") (pinfunction "1_1") (pintype "passive"))
      (node (ref "U6") (pin "8") (pinfunction "OUT_8") (pintype "output"))
    )
    (net (code "46") (name "Net-(U6D--IN)") (class "Default")
      (node (ref "C10") (pin "1") (pinfunction "1_1") (pintype "passive"))
      (node (ref "R32") (pin "2") (pinfunction "2_2") (pintype "passive"))
      (node (ref "R33") (pin "1") (pinfunction "1_1") (pintype "passive"))
      (node (ref "U6") (pin "13") (pinfunction "-IN_13") (pintype "input"))
      (node (ref "VR4") (pin "P$3") (pinfunction "A_P$3") (pintype "passive"))
    )
    (net (code "47") (name "Net-(U6D-OUT)") (class "Default")
      (node (ref "C10") (pin "2") (pinfunction "2_2") (pintype "passive"))
      (node (ref "R34") (pin "1") (pinfunction "1_1") (pintype "passive"))
      (node (ref "U6") (pin "14") (pinfunction "OUT_14") (pintype "output"))
    )
    (net (code "48") (name "Net-(U7A--IN)") (class "Default")
      (node (ref "R47") (pin "1") (pinfunction "1_1") (pintype "passive"))
      (node (ref "U7") (pin "2") (pinfunction "-IN_2") (pintype "input"))
      (node (ref "VR8") (pin "P$1") (pinfunction "E_P$1") (pintype "passive"))
    )
    (net (code "49") (name "Net-(U7A-OUT)") (class "Default")
      (node (ref "R47") (pin "2") (pinfunction "2_2") (pintype "passive"))
      (node (ref "R48") (pin "1") (pinfunction "1_1") (pintype "passive"))
      (node (ref "U7") (pin "1") (pinfunction "OUT_1") (pintype "output"))
    )
    (net (code "50") (name "Net-(U7B--IN)") (class "Default")
      (node (ref "R43") (pin "1") (pinfunction "1_1") (pintype "passive"))
      (node (ref "U7") (pin "6") (pinfunction "-IN_6") (pintype "input"))
      (node (ref "VR7") (pin "P$1") (pinfunction "E_P$1") (pintype "passive"))
    )
    (net (code "51") (name "Net-(U7B-OUT)") (class "Default")
      (node (ref "R43") (pin "2") (pinfunction "2_2") (pintype "passive"))
      (node (ref "R44") (pin "1") (pinfunction "1_1") (pintype "passive"))
      (node (ref "U7") (pin "7") (pinfunction "OUT_7") (pintype "output"))
    )
    (net (code "52") (name "Net-(U7C--IN)") (class "Default")
      (node (ref "C13") (pin "1") (pinfunction "1_1") (pintype "passive"))
      (node (ref "R44") (pin "2") (pinfunction "2_2") (pintype "passive"))
      (node (ref "R46") (pin "1") (pinfunction "1_1") (pintype "passive"))
      (node (ref "U7") (pin "9") (pinfunction "-IN_9") (pintype "input"))
      (node (ref "VR7") (pin "P$3") (pinfunction "A_P$3") (pintype "passive"))
    )
    (net (code "53") (name "Net-(U7C-OUT)") (class "Default")
      (node (ref "C13") (pin "2") (pinfunction "2_2") (pintype "passive"))
      (node (ref "R45") (pin "1") (pinfunction "1_1") (pintype "passive"))
      (node (ref "U7") (pin "8") (pinfunction "OUT_8") (pintype "output"))
    )
    (net (code "54") (name "Net-(U7D--IN)") (class "Default")
      (node (ref "C14") (pin "1") (pinfunction "1_1") (pintype "passive"))
      (node (ref "R48") (pin "2") (pinfunction "2_2") (pintype "passive"))
      (node (ref "R49") (pin "1") (pinfunction "1_1") (pintype "passive"))
      (node (ref "U7") (pin "13") (pinfunction "-IN_13") (pintype "input"))
      (node (ref "VR8") (pin "P$3") (pinfunction "A_P$3") (pintype "passive"))
    )
    (net (code "55") (name "Net-(U7D-OUT)") (class "Default")
      (node (ref "C14") (pin "2") (pinfunction "2_2") (pintype "passive"))
      (node (ref "R50") (pin "1") (pinfunction "1_1") (pintype "passive"))
      (node (ref "U7") (pin "14") (pinfunction "OUT_14") (pintype "output"))
    )
    (net (code "56") (name "Net-(UNITY_IN_1-TIP)") (class "Default")
      (node (ref "R1") (pin "1") (pinfunction "1_1") (pintype "passive"))
      (node (ref "UNITY_IN_1") (pin "P$1_TIP") (pinfunction "TIP_P$1_TIP") (pintype "passive"))
    )
    (net (code "57") (name "Net-(UNITY_IN_2-TIP)") (class "Default")
      (node (ref "R2") (pin "1") (pinfunction "1_1") (pintype "passive"))
      (node (ref "UNITY_IN_2") (pin "P$1_TIP") (pinfunction "TIP_P$1_TIP") (pintype "passive"))
    )
    (net (code "58") (name "Net-(UNITY_IN_3-TIP)") (class "Default")
      (node (ref "R7") (pin "1") (pinfunction "1_1") (pintype "passive"))
      (node (ref "UNITY_IN_3") (pin "P$1_TIP") (pinfunction "TIP_P$1_TIP") (pintype "passive"))
    )
    (net (code "59") (name "Net-(UNITY_IN_4-TIP)") (class "Default")
      (node (ref "R14") (pin "1") (pinfunction "1_1") (pintype "passive"))
      (node (ref "UNITY_IN_4") (pin "P$1_TIP") (pinfunction "TIP_P$1_TIP") (pintype "passive"))
    )
    (net (code "60") (name "Net-(UNITY_IN_5-TIP)") (class "Default")
      (node (ref "R15") (pin "1") (pinfunction "1_1") (pintype "passive"))
      (node (ref "UNITY_IN_5") (pin "P$1_TIP") (pinfunction "TIP_P$1_TIP") (pintype "passive"))
    )
    (net (code "61") (name "Net-(UNITY_IN_6-TIP)") (class "Default")
      (node (ref "R16") (pin "1") (pinfunction "1_1") (pintype "passive"))
      (node (ref "UNITY_IN_6") (pin "P$1_TIP") (pinfunction "TIP_P$1_TIP") (pintype "passive"))
    )
    (net (code "62") (name "Net-(UNITY_OUT_1-TIP)") (class "Default")
      (node (ref "R53") (pin "2") (pinfunction "2_2") (pintype "passive"))
      (node (ref "UNITY_OUT_1") (pin "P$1_TIP") (pinfunction "TIP_P$1_TIP") (pintype "passive"))
    )
    (net (code "63") (name "Net-(UNITY_OUT_2-TIP)") (class "Default")
      (node (ref "R52") (pin "2") (pinfunction "2_2") (pintype "passive"))
      (node (ref "UNITY_OUT_2") (pin "P$1_TIP") (pinfunction "TIP_P$1_TIP") (pintype "passive"))
    )
    (net (code "64") (name "Net-(VR1-S)") (class "Default")
      (node (ref "R3") (pin "2") (pinfunction "2_2") (pintype "passive"))
      (node (ref "VR1") (pin "P$2") (pinfunction "S_P$2") (pintype "passive"))
    )
    (net (code "65") (name "Net-(VR2-S)") (class "Default")
      (node (ref "R4") (pin "2") (pinfunction "2_2") (pintype "passive"))
      (node (ref "VR2") (pin "P$2") (pinfunction "S_P$2") (pintype "passive"))
    )
    (net (code "66") (name "Net-(VR3-S)") (class "Default")
      (node (ref "R5") (pin "2") (pinfunction "2_2") (pintype "passive"))
      (node (ref "VR3") (pin "P$2") (pinfunction "S_P$2") (pintype "passive"))
    )
    (net (code "67") (name "Net-(VR4-S)") (class "Default")
      (node (ref "R6") (pin "2") (pinfunction "2_2") (pintype "passive"))
      (node (ref "VR4") (pin "P$2") (pinfunction "S_P$2") (pintype "passive"))
    )
    (net (code "68") (name "Net-(VR5-S)") (class "Default")
      (node (ref "R9") (pin "2") (pinfunction "2_2") (pintype "passive"))
      (node (ref "VR5") (pin "P$2") (pinfunction "S_P$2") (pintype "passive"))
    )
    (net (code "69") (name "Net-(VR6-S)") (class "Default")
      (node (ref "R10") (pin "2") (pinfunction "2_2") (pintype "passive"))
      (node (ref "VR6") (pin "P$2") (pinfunction "S_P$2") (pintype "passive"))
    )
    (net (code "70") (name "Net-(VR7-S)") (class "Default")
      (node (ref "R11") (pin "2") (pinfunction "2_2") (pintype "passive"))
      (node (ref "VR7") (pin "P$2") (pinfunction "S_P$2") (pintype "passive"))
    )
    (net (code "71") (name "Net-(VR8-S)") (class "Default")
      (node (ref "R12") (pin "2") (pinfunction "2_2") (pintype "passive"))
      (node (ref "VR8") (pin "P$2") (pinfunction "S_P$2") (pintype "passive"))
    )
    (net (code "72") (name "VCC") (class "Default")
      (node (ref "C1") (pin "1") (pinfunction "1_1") (pintype "passive"))
      (node (ref "C20") (pin "1") (pinfunction "1_1") (pintype "passive"))
      (node (ref "C21") (pin "1") (pinfunction "1_1") (pintype "passive"))
      (node (ref "C22") (pin "1") (pinfunction "1_1") (pintype "passive"))
      (node (ref "C23") (pin "1") (pinfunction "1_1") (pintype "passive"))
      (node (ref "C3") (pin "1") (pinfunction "1_1") (pintype "passive"))
      (node (ref "C4") (pin "1") (pinfunction "1_1") (pintype "passive"))
      (node (ref "D1") (pin "C") (pinfunction "C_C") (pintype "passive"))
    )
    (net (code "73") (name "VEE") (class "Default")
      (node (ref "C15") (pin "2") (pinfunction "2_2") (pintype "passive"))
      (node (ref "C16") (pin "2") (pinfunction "2_2") (pintype "passive"))
      (node (ref "C17") (pin "2") (pinfunction "2_2") (pintype "passive"))
      (node (ref "C18") (pin "2") (pinfunction "2_2") (pintype "passive"))
      (node (ref "C2") (pin "2") (pinfunction "2_2") (pintype "passive"))
      (node (ref "C6") (pin "2") (pinfunction "2_2") (pintype "passive"))
      (node (ref "C7") (pin "2") (pinfunction "2_2") (pintype "passive"))
      (node (ref "D2") (pin "A") (pinfunction "A_A") (pintype "passive"))
    )
    (net (code "74") (name "unconnected-(IN_1-SWITCH-PadP$2_SWITCH)") (class "Default")
      (node (ref "IN_1") (pin "P$2_SWITCH") (pinfunction "SWITCH_P$2_SWITCH") (pintype "passive"))
    )
    (net (code "75") (name "unconnected-(IN_2-SWITCH-PadP$2_SWITCH)") (class "Default")
      (node (ref "IN_2") (pin "P$2_SWITCH") (pinfunction "SWITCH_P$2_SWITCH") (pintype "passive"))
    )
    (net (code "76") (name "unconnected-(OUT_1A-SWITCH-PadP$2_SWITCH)") (class "Default")
      (node (ref "OUT_1A") (pin "P$2_SWITCH") (pinfunction "SWITCH_P$2_SWITCH") (pintype "passive"))
    )
    (net (code "77") (name "unconnected-(OUT_1B-SWITCH-PadP$2_SWITCH)") (class "Default")
      (node (ref "OUT_1B") (pin "P$2_SWITCH") (pinfunction "SWITCH_P$2_SWITCH") (pintype "passive"))
    )
    (net (code "78") (name "unconnected-(OUT_1C-SWITCH-PadP$2_SWITCH)") (class "Default")
      (node (ref "OUT_1C") (pin "P$2_SWITCH") (pinfunction "SWITCH_P$2_SWITCH") (pintype "passive"))
    )
    (net (code "79") (name "unconnected-(OUT_1D-SWITCH-PadP$2_SWITCH)") (class "Default")
      (node (ref "OUT_1D") (pin "P$2_SWITCH") (pinfunction "SWITCH_P$2_SWITCH") (pintype "passive"))
    )
    (net (code "80") (name "unconnected-(OUT_2A-SWITCH-PadP$2_SWITCH)") (class "Default")
      (node (ref "OUT_2A") (pin "P$2_SWITCH") (pinfunction "SWITCH_P$2_SWITCH") (pintype "passive"))
    )
    (net (code "81") (name "unconnected-(OUT_2B-SWITCH-PadP$2_SWITCH)") (class "Default")
      (node (ref "OUT_2B") (pin "P$2_SWITCH") (pinfunction "SWITCH_P$2_SWITCH") (pintype "passive"))
    )
    (net (code "82") (name "unconnected-(OUT_2C-SWITCH-PadP$2_SWITCH)") (class "Default")
      (node (ref "OUT_2C") (pin "P$2_SWITCH") (pinfunction "SWITCH_P$2_SWITCH") (pintype "passive"))
    )
    (net (code "83") (name "unconnected-(OUT_2D-SWITCH-PadP$2_SWITCH)") (class "Default")
      (node (ref "OUT_2D") (pin "P$2_SWITCH") (pinfunction "SWITCH_P$2_SWITCH") (pintype "passive"))
    )
    (net (code "84") (name "unconnected-(UNITY_IN_1-SWITCH-PadP$2_SWITCH)") (class "Default")
      (node (ref "UNITY_IN_1") (pin "P$2_SWITCH") (pinfunction "SWITCH_P$2_SWITCH") (pintype "passive"))
    )
    (net (code "85") (name "unconnected-(UNITY_IN_2-SWITCH-PadP$2_SWITCH)") (class "Default")
      (node (ref "UNITY_IN_2") (pin "P$2_SWITCH") (pinfunction "SWITCH_P$2_SWITCH") (pintype "passive"))
    )
    (net (code "86") (name "unconnected-(UNITY_IN_3-SWITCH-PadP$2_SWITCH)") (class "Default")
      (node (ref "UNITY_IN_3") (pin "P$2_SWITCH") (pinfunction "SWITCH_P$2_SWITCH") (pintype "passive"))
    )
    (net (code "87") (name "unconnected-(UNITY_IN_4-SWITCH-PadP$2_SWITCH)") (class "Default")
      (node (ref "UNITY_IN_4") (pin "P$2_SWITCH") (pinfunction "SWITCH_P$2_SWITCH") (pintype "passive"))
    )
    (net (code "88") (name "unconnected-(UNITY_IN_5-SWITCH-PadP$2_SWITCH)") (class "Default")
      (node (ref "UNITY_IN_5") (pin "P$2_SWITCH") (pinfunction "SWITCH_P$2_SWITCH") (pintype "passive"))
    )
    (net (code "89") (name "unconnected-(UNITY_IN_6-SWITCH-PadP$2_SWITCH)") (class "Default")
      (node (ref "UNITY_IN_6") (pin "P$2_SWITCH") (pinfunction "SWITCH_P$2_SWITCH") (pintype "passive"))
    )
    (net (code "90") (name "unconnected-(UNITY_OUT_1-SWITCH-PadP$2_SWITCH)") (class "Default")
      (node (ref "UNITY_OUT_1") (pin "P$2_SWITCH") (pinfunction "SWITCH_P$2_SWITCH") (pintype "passive"))
    )
    (net (code "91") (name "unconnected-(UNITY_OUT_2-SWITCH-PadP$2_SWITCH)") (class "Default")
      (node (ref "UNITY_OUT_2") (pin "P$2_SWITCH") (pinfunction "SWITCH_P$2_SWITCH") (pintype "passive"))
    )
  )
)
